# SMI_Bank_12.net
KiCad netlist of a schematic drawn in Altium Designer
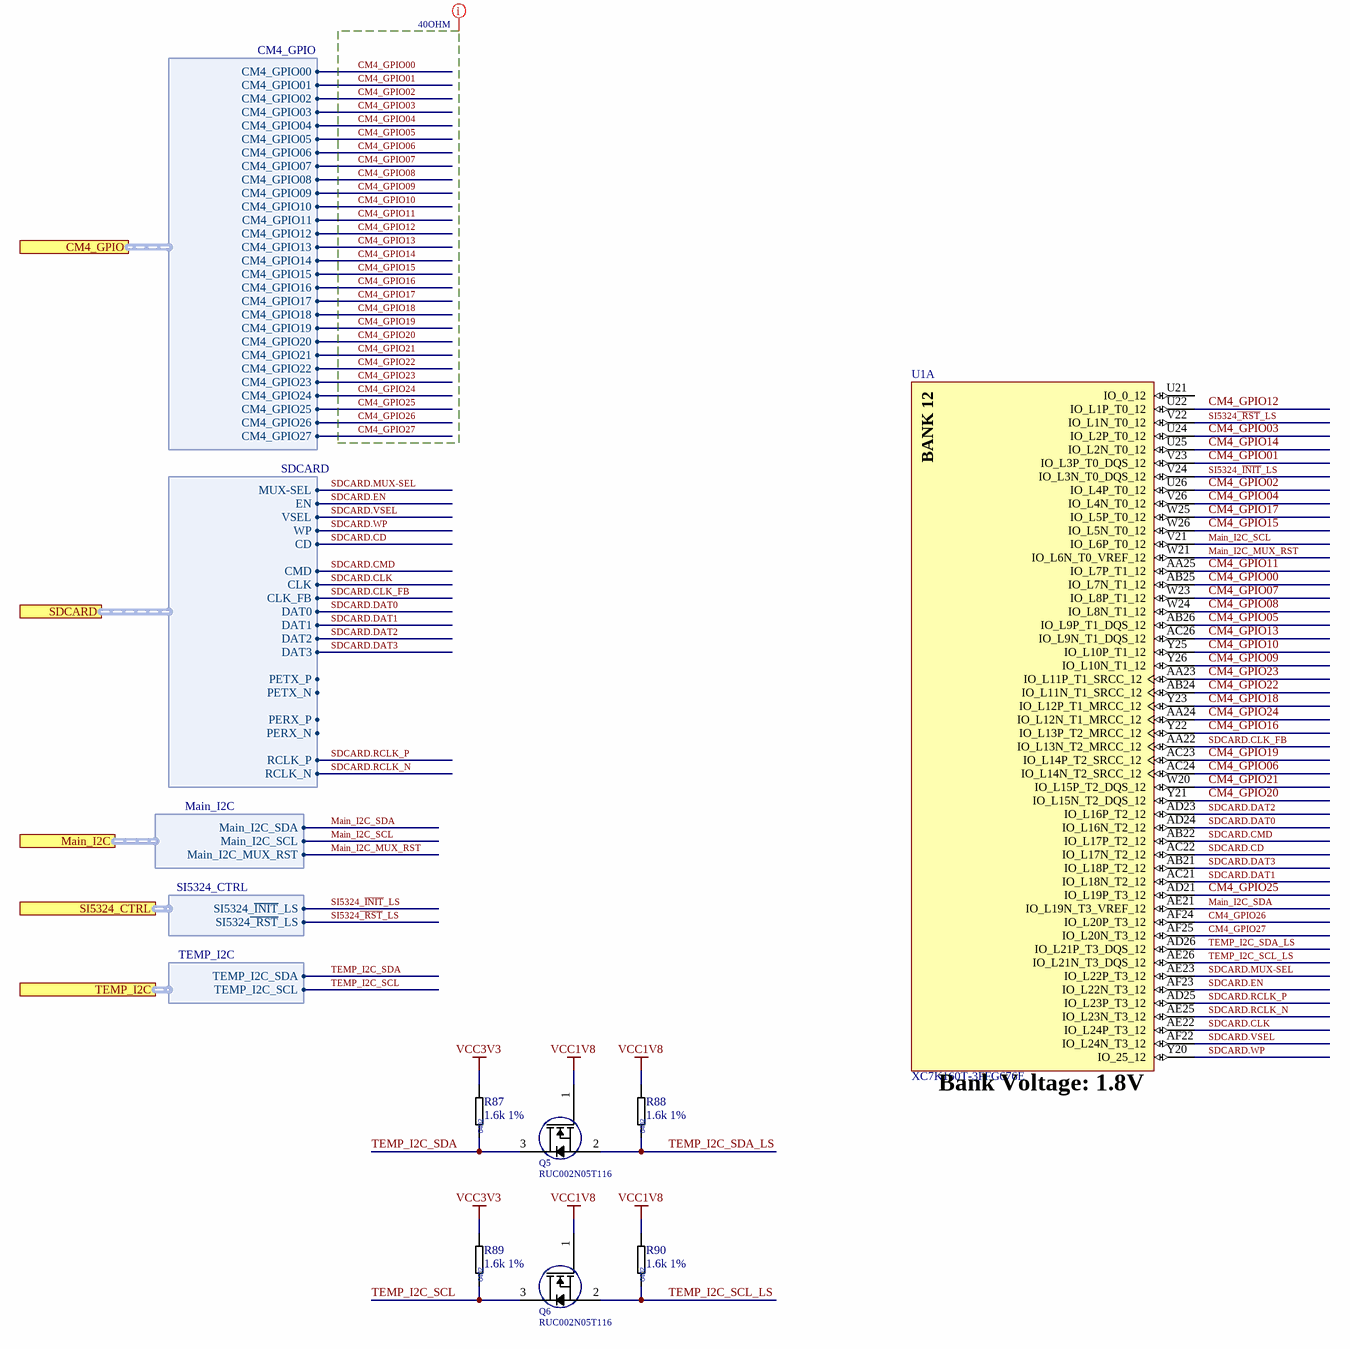
[diagram p0: SMI Bank 12.SchDoc]

(export (version "E")
  (design (tool "Eeschema 10.0.6"))
  (components
    (comp (ref "Q5")
      (value "RUC002N05T116")
      (footprint "trans:SOT95P251X112-3N")
      (description "MOSFET N-Ch 1.2 VGS Spec")
      (libsource (lib "Trans") (part "RUC002N05T116_MOSFET N-Ch 1.2 VGS Spec"))
    )
    (comp (ref "Q6")
      (value "RUC002N05T116")
      (footprint "trans:SOT95P251X112-3N")
      (description "MOSFET N-Ch 1.2 VGS Spec")
      (libsource (lib "Trans") (part "RUC002N05T116_MOSFET N-Ch 1.2 VGS Spec"))
    )
    (comp (ref "R87")
      (value "1.6k 1%")
      (footprint "RES_0402_L")
      (description "Thick Film Resistors - SMD 1.6kOhm 1%")
      (libsource (lib "Res") (part "RES_0402_1.6k_1%"))
    )
    (comp (ref "R88")
      (value "1.6k 1%")
      (footprint "RES_0402_L")
      (description "Thick Film Resistors - SMD 1.6kOhm 1%")
      (libsource (lib "Res") (part "RES_0402_1.6k_1%"))
    )
    (comp (ref "R89")
      (value "1.6k 1%")
      (footprint "RES_0402_L")
      (description "Thick Film Resistors - SMD 1.6kOhm 1%")
      (libsource (lib "Res") (part "RES_0402_1.6k_1%"))
    )
    (comp (ref "R90")
      (value "1.6k 1%")
      (footprint "RES_0402_L")
      (description "Thick Film Resistors - SMD 1.6kOhm 1%")
      (libsource (lib "Res") (part "RES_0402_1.6k_1%"))
    )
    (comp (ref "U1")
      (value "XC7K160T-3FFG676E")
      (footprint "Digital:BGA100P2700X2700X317-676N")
      (description "Kintex-7 FPGA, 400 User I/Os, 8 GTX, 676-Ball BGA, Speed Grade 3, Extended Grade, Pb-Free")
      (libsource (lib "Digital") (part "XC7K160T-3FFG676E_Kintex-7 FPGA, 400 User I/Os, 8 GTX, FFG676"))
    )
  )
  (nets
    (net (code "6") (name "/CM4_GPIO00") (class "Default")
      (node (ref "U1") (pin "AB25") (pinfunction "IO_L7N_T1_12_AB25") (pintype "bidirectional"))
    )
    (net (code "7") (name "/CM4_GPIO01") (class "Default")
      (node (ref "U1") (pin "V23") (pinfunction "IO_L3P_T0_DQS_12_V23") (pintype "bidirectional"))
    )
    (net (code "8") (name "/CM4_GPIO02") (class "Default")
      (node (ref "U1") (pin "U26") (pinfunction "IO_L4P_T0_12_U26") (pintype "bidirectional"))
    )
    (net (code "9") (name "/CM4_GPIO03") (class "Default")
      (node (ref "U1") (pin "U24") (pinfunction "IO_L2P_T0_12_U24") (pintype "bidirectional"))
    )
    (net (code "10") (name "/CM4_GPIO04") (class "Default")
      (node (ref "U1") (pin "V26") (pinfunction "IO_L4N_T0_12_V26") (pintype "bidirectional"))
    )
    (net (code "11") (name "/CM4_GPIO05") (class "Default")
      (node (ref "U1") (pin "AB26") (pinfunction "IO_L9P_T1_DQS_12_AB26") (pintype "bidirectional"))
    )
    (net (code "12") (name "/CM4_GPIO06") (class "Default")
      (node (ref "U1") (pin "AC24") (pinfunction "IO_L14N_T2_SRCC_12_AC24") (pintype "bidirectional"))
    )
    (net (code "13") (name "/CM4_GPIO07") (class "Default")
      (node (ref "U1") (pin "W23") (pinfunction "IO_L8P_T1_12_W23") (pintype "bidirectional"))
    )
    (net (code "14") (name "/CM4_GPIO08") (class "Default")
      (node (ref "U1") (pin "W24") (pinfunction "IO_L8N_T1_12_W24") (pintype "bidirectional"))
    )
    (net (code "15") (name "/CM4_GPIO09") (class "Default")
      (node (ref "U1") (pin "Y26") (pinfunction "IO_L10N_T1_12_Y26") (pintype "bidirectional"))
    )
    (net (code "16") (name "/CM4_GPIO10") (class "Default")
      (node (ref "U1") (pin "Y25") (pinfunction "IO_L10P_T1_12_Y25") (pintype "bidirectional"))
    )
    (net (code "17") (name "/CM4_GPIO11") (class "Default")
      (node (ref "U1") (pin "AA25") (pinfunction "IO_L7P_T1_12_AA25") (pintype "bidirectional"))
    )
    (net (code "18") (name "/CM4_GPIO12") (class "Default")
      (node (ref "U1") (pin "U22") (pinfunction "IO_L1P_T0_12_U22") (pintype "bidirectional"))
    )
    (net (code "19") (name "/CM4_GPIO13") (class "Default")
      (node (ref "U1") (pin "AC26") (pinfunction "IO_L9N_T1_DQS_12_AC26") (pintype "bidirectional"))
    )
    (net (code "20") (name "/CM4_GPIO14") (class "Default")
      (node (ref "U1") (pin "U25") (pinfunction "IO_L2N_T0_12_U25") (pintype "bidirectional"))
    )
    (net (code "21") (name "/CM4_GPIO15") (class "Default")
      (node (ref "U1") (pin "W26") (pinfunction "IO_L5N_T0_12_W26") (pintype "bidirectional"))
    )
    (net (code "22") (name "/CM4_GPIO16") (class "Default")
      (node (ref "U1") (pin "Y22") (pinfunction "IO_L13P_T2_MRCC_12_Y22") (pintype "bidirectional"))
    )
    (net (code "23") (name "/CM4_GPIO17") (class "Default")
      (node (ref "U1") (pin "W25") (pinfunction "IO_L5P_T0_12_W25") (pintype "bidirectional"))
    )
    (net (code "24") (name "/CM4_GPIO18") (class "Default")
      (node (ref "U1") (pin "Y23") (pinfunction "IO_L12P_T1_MRCC_12_Y23") (pintype "bidirectional"))
    )
    (net (code "25") (name "/CM4_GPIO19") (class "Default")
      (node (ref "U1") (pin "AC23") (pinfunction "IO_L14P_T2_SRCC_12_AC23") (pintype "bidirectional"))
    )
    (net (code "26") (name "/CM4_GPIO20") (class "Default")
      (node (ref "U1") (pin "Y21") (pinfunction "IO_L15N_T2_DQS_12_Y21") (pintype "bidirectional"))
    )
    (net (code "27") (name "/CM4_GPIO21") (class "Default")
      (node (ref "U1") (pin "W20") (pinfunction "IO_L15P_T2_DQS_12_W20") (pintype "bidirectional"))
    )
    (net (code "28") (name "/CM4_GPIO22") (class "Default")
      (node (ref "U1") (pin "AB24") (pinfunction "IO_L11N_T1_SRCC_12_AB24") (pintype "bidirectional"))
    )
    (net (code "29") (name "/CM4_GPIO23") (class "Default")
      (node (ref "U1") (pin "AA23") (pinfunction "IO_L11P_T1_SRCC_12_AA23") (pintype "bidirectional"))
    )
    (net (code "30") (name "/CM4_GPIO24") (class "Default")
      (node (ref "U1") (pin "AA24") (pinfunction "IO_L12N_T1_MRCC_12_AA24") (pintype "bidirectional"))
    )
    (net (code "31") (name "/CM4_GPIO25") (class "Default")
      (node (ref "U1") (pin "AD21") (pinfunction "IO_L19P_T3_12_AD21") (pintype "bidirectional"))
    )
    (net (code "32") (name "/CM4_GPIO26") (class "Default")
      (node (ref "U1") (pin "AF24") (pinfunction "IO_L20P_T3_12_AF24") (pintype "bidirectional"))
    )
    (net (code "33") (name "/CM4_GPIO27") (class "Default")
      (node (ref "U1") (pin "AF25") (pinfunction "IO_L20N_T3_12_AF25") (pintype "bidirectional"))
    )
    (net (code "34") (name "/Main_I2C_MUX_RST") (class "Default")
      (node (ref "U1") (pin "W21") (pinfunction "IO_L6N_T0_VREF_12_W21") (pintype "bidirectional"))
    )
    (net (code "35") (name "/Main_I2C_SCL") (class "Default")
      (node (ref "U1") (pin "V21") (pinfunction "IO_L6P_T0_12_V21") (pintype "bidirectional"))
    )
    (net (code "36") (name "/Main_I2C_SDA") (class "Default")
      (node (ref "U1") (pin "AE21") (pinfunction "IO_L19N_T3_VREF_12_AE21") (pintype "bidirectional"))
    )
    (net (code "37") (name "/SDCARD.CD") (class "Default")
      (node (ref "U1") (pin "AC22") (pinfunction "IO_L17N_T2_12_AC22") (pintype "bidirectional"))
    )
    (net (code "38") (name "/SDCARD.CLK") (class "Default")
      (node (ref "U1") (pin "AE22") (pinfunction "IO_L24P_T3_12_AE22") (pintype "bidirectional"))
    )
    (net (code "39") (name "/SDCARD.CLK_FB") (class "Default")
      (node (ref "U1") (pin "AA22") (pinfunction "IO_L13N_T2_MRCC_12_AA22") (pintype "bidirectional"))
    )
    (net (code "40") (name "/SDCARD.CMD") (class "Default")
      (node (ref "U1") (pin "AB22") (pinfunction "IO_L17P_T2_12_AB22") (pintype "bidirectional"))
    )
    (net (code "41") (name "/SDCARD.DAT0") (class "Default")
      (node (ref "U1") (pin "AD24") (pinfunction "IO_L16N_T2_12_AD24") (pintype "bidirectional"))
    )
    (net (code "42") (name "/SDCARD.DAT1") (class "Default")
      (node (ref "U1") (pin "AC21") (pinfunction "IO_L18N_T2_12_AC21") (pintype "bidirectional"))
    )
    (net (code "43") (name "/SDCARD.DAT2") (class "Default")
      (node (ref "U1") (pin "AD23") (pinfunction "IO_L16P_T2_12_AD23") (pintype "bidirectional"))
    )
    (net (code "44") (name "/SDCARD.DAT3") (class "Default")
      (node (ref "U1") (pin "AB21") (pinfunction "IO_L18P_T2_12_AB21") (pintype "bidirectional"))
    )
    (net (code "45") (name "/SDCARD.EN") (class "Default")
      (node (ref "U1") (pin "AF23") (pinfunction "IO_L22N_T3_12_AF23") (pintype "bidirectional"))
    )
    (net (code "46") (name "/SDCARD.MUX-SEL") (class "Default")
      (node (ref "U1") (pin "AE23") (pinfunction "IO_L22P_T3_12_AE23") (pintype "bidirectional"))
    )
    (net (code "47") (name "/SDCARD.RCLK_N") (class "Default")
      (node (ref "U1") (pin "AE25") (pinfunction "IO_L23N_T3_12_AE25") (pintype "bidirectional"))
    )
    (net (code "48") (name "/SDCARD.RCLK_P") (class "Default")
      (node (ref "U1") (pin "AD25") (pinfunction "IO_L23P_T3_12_AD25") (pintype "bidirectional"))
    )
    (net (code "49") (name "/SDCARD.VSEL") (class "Default")
      (node (ref "U1") (pin "AF22") (pinfunction "IO_L24N_T3_12_AF22") (pintype "bidirectional"))
    )
    (net (code "50") (name "/SDCARD.WP") (class "Default")
      (node (ref "U1") (pin "Y20") (pinfunction "IO_25_12_Y20") (pintype "bidirectional"))
    )
    (net (code "51") (name "/SI5324_~{INIT}_LS") (class "Default")
      (node (ref "U1") (pin "V24") (pinfunction "IO_L3N_T0_DQS_12_V24") (pintype "bidirectional"))
    )
    (net (code "52") (name "/SI5324~{_RST}_LS") (class "Default")
      (node (ref "U1") (pin "V22") (pinfunction "IO_L1N_T0_12_V22") (pintype "bidirectional"))
    )
    (net (code "53") (name "/TEMP_I2C_SCL") (class "Default")
      (node (ref "Q6") (pin "3") (pinfunction "S_3") (pintype "passive"))
      (node (ref "R89") (pin "1") (pinfunction "1_1") (pintype "passive"))
    )
    (net (code "54") (name "/TEMP_I2C_SCL_LS") (class "Default")
      (node (ref "Q6") (pin "2") (pinfunction "D_2") (pintype "passive"))
      (node (ref "R90") (pin "1") (pinfunction "1_1") (pintype "passive"))
      (node (ref "U1") (pin "AE26") (pinfunction "IO_L21N_T3_DQS_12_AE26") (pintype "bidirectional"))
    )
    (net (code "55") (name "/TEMP_I2C_SDA") (class "Default")
      (node (ref "Q5") (pin "3") (pinfunction "S_3") (pintype "passive"))
      (node (ref "R87") (pin "1") (pinfunction "1_1") (pintype "passive"))
    )
    (net (code "56") (name "/TEMP_I2C_SDA_LS") (class "Default")
      (node (ref "Q5") (pin "2") (pinfunction "D_2") (pintype "passive"))
      (node (ref "R88") (pin "1") (pinfunction "1_1") (pintype "passive"))
      (node (ref "U1") (pin "AD26") (pinfunction "IO_L21P_T3_DQS_12_AD26") (pintype "bidirectional"))
    )
    (net (code "62") (name "VCC1V8") (class "Default")
      (node (ref "Q5") (pin "1") (pinfunction "G_1") (pintype "passive"))
      (node (ref "Q6") (pin "1") (pinfunction "G_1") (pintype "passive"))
      (node (ref "R88") (pin "2") (pinfunction "2_2") (pintype "passive"))
      (node (ref "R90") (pin "2") (pinfunction "2_2") (pintype "passive"))
    )
    (net (code "63") (name "VCC3V3") (class "Default")
      (node (ref "R87") (pin "2") (pinfunction "2_2") (pintype "passive"))
      (node (ref "R89") (pin "2") (pinfunction "2_2") (pintype "passive"))
    )
    (net (code "64") (name "unconnected-(U1A-IO_0_12-PadU21)") (class "Default")
      (node (ref "U1") (pin "U21") (pinfunction "IO_0_12_U21") (pintype "bidirectional"))
    )
  )
)
